# motoko_5_0.net
KiCad netlist of a schematic drawn in EAGLE
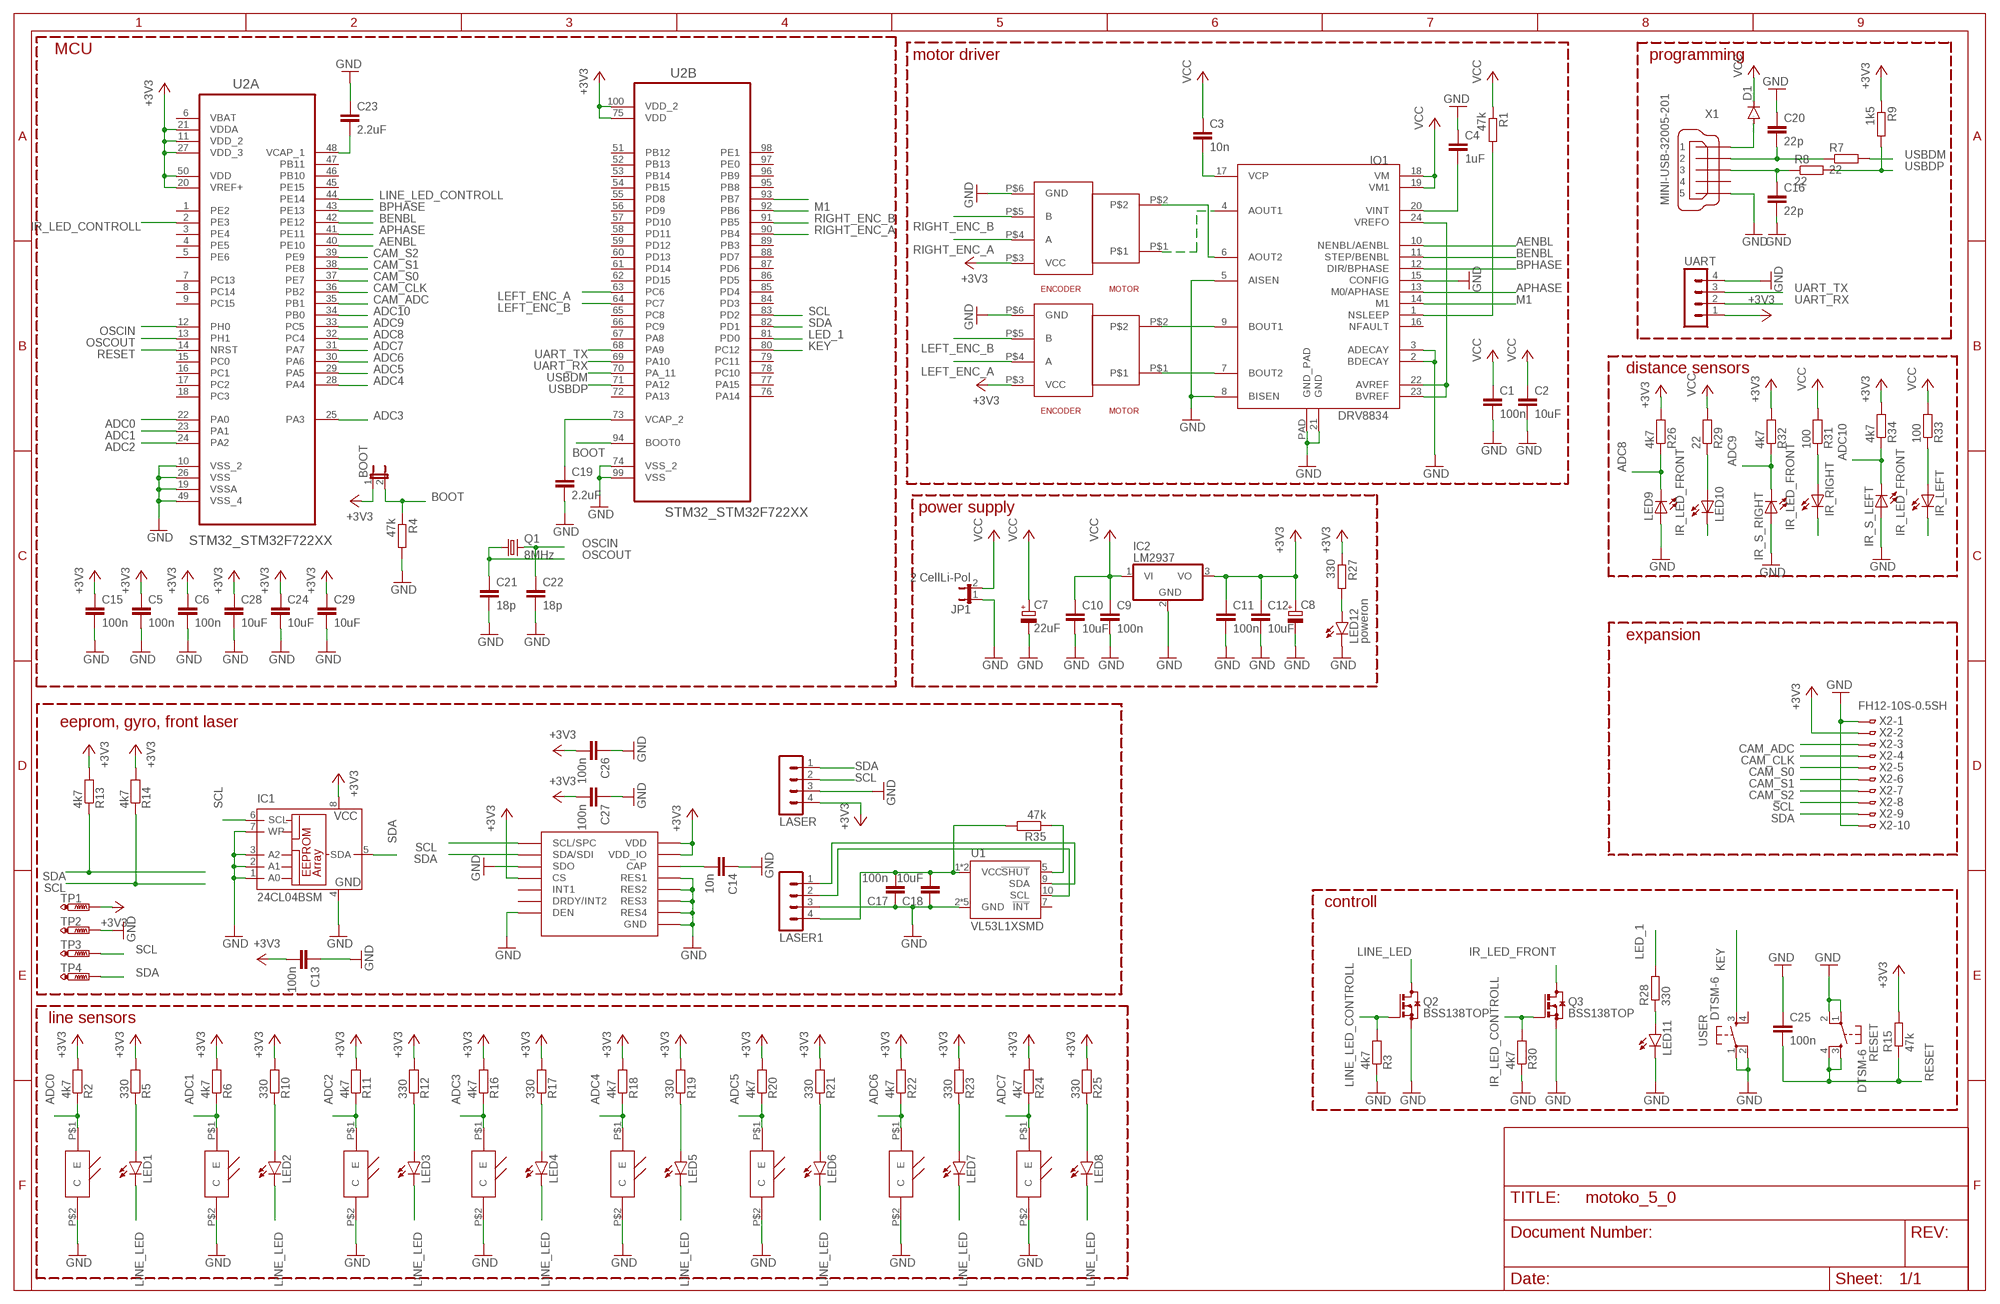
[diagram p0: schematic, sheet 1]

(export (version "E")
  (design (tool "Eeschema 10.0.6"))
  (components
    (comp (ref "BOOT")
      (value "JP1E")
      (footprint "eagle-import:JP1")
      (libsource (lib "eagle-import") (part "JP1E"))
    )
    (comp (ref "C1")
      (value "100n")
      (footprint "eagle-import:C1206")
      (libsource (lib "eagle-import") (part "C-EUC1206"))
    )
    (comp (ref "C2")
      (value "10uF")
      (footprint "eagle-import:C1206")
      (libsource (lib "eagle-import") (part "C-EUC1206"))
    )
    (comp (ref "C3")
      (value "10n")
      (footprint "eagle-import:C1206")
      (libsource (lib "eagle-import") (part "C-EUC1206"))
    )
    (comp (ref "C4")
      (value "1uF")
      (footprint "eagle-import:C1206")
      (libsource (lib "eagle-import") (part "C-EUC1206"))
    )
    (comp (ref "C5")
      (value "100n")
      (footprint "eagle-import:C0805")
      (libsource (lib "eagle-import") (part "C-EUC0805"))
    )
    (comp (ref "C6")
      (value "100n")
      (footprint "eagle-import:C0805")
      (libsource (lib "eagle-import") (part "C-EUC0805"))
    )
    (comp (ref "C7")
      (value "22uF")
      (footprint "eagle-import:153CLV-0505")
      (libsource (lib "eagle-import") (part "resistor_348_CPOL-EU153CLV-0505"))
    )
    (comp (ref "C8")
      (value "CPOL-EU140CLH-1010")
      (footprint "eagle-import:140CLH-1010")
      (libsource (lib "eagle-import") (part "CPOL-EU140CLH-1010"))
    )
    (comp (ref "C9")
      (value "100n")
      (footprint "eagle-import:C0805")
      (libsource (lib "eagle-import") (part "C-EUC0805"))
    )
    (comp (ref "C10")
      (value "10uF")
      (footprint "eagle-import:C0805")
      (libsource (lib "eagle-import") (part "C-EUC0805"))
    )
    (comp (ref "C11")
      (value "100n")
      (footprint "eagle-import:C0805")
      (libsource (lib "eagle-import") (part "C-EUC0805"))
    )
    (comp (ref "C12")
      (value "10uF")
      (footprint "eagle-import:C0805")
      (libsource (lib "eagle-import") (part "C-EUC0805"))
    )
    (comp (ref "C13")
      (value "100n")
      (footprint "eagle-import:C0805")
      (libsource (lib "eagle-import") (part "C-EUC0805"))
    )
    (comp (ref "C14")
      (value "10n")
      (footprint "eagle-import:C0805")
      (libsource (lib "eagle-import") (part "C-EUC0805"))
    )
    (comp (ref "C15")
      (value "100n")
      (footprint "eagle-import:C0805")
      (libsource (lib "eagle-import") (part "C-EUC0805"))
    )
    (comp (ref "C16")
      (value "22p")
      (footprint "eagle-import:C0805")
      (libsource (lib "eagle-import") (part "C-EUC0805"))
    )
    (comp (ref "C17")
      (value "100n")
      (footprint "eagle-import:C0805")
      (libsource (lib "eagle-import") (part "C-EUC0805"))
    )
    (comp (ref "C18")
      (value "10uF")
      (footprint "eagle-import:C0805")
      (libsource (lib "eagle-import") (part "C-EUC0805"))
    )
    (comp (ref "C19")
      (value "2.2uF")
      (footprint "eagle-import:C0805")
      (libsource (lib "eagle-import") (part "C-EUC0805"))
    )
    (comp (ref "C20")
      (value "22p")
      (footprint "eagle-import:C0805")
      (libsource (lib "eagle-import") (part "C-EUC0805"))
    )
    (comp (ref "C21")
      (value "18p")
      (footprint "eagle-import:C0805")
      (libsource (lib "eagle-import") (part "C-EUC0805"))
    )
    (comp (ref "C22")
      (value "18p")
      (footprint "eagle-import:C0805")
      (libsource (lib "eagle-import") (part "C-EUC0805"))
    )
    (comp (ref "C23")
      (value "2.2uF")
      (footprint "eagle-import:C0805")
      (libsource (lib "eagle-import") (part "C-EUC0805"))
    )
    (comp (ref "C24")
      (value "10uF")
      (footprint "eagle-import:C0805")
      (libsource (lib "eagle-import") (part "C-EUC0805"))
    )
    (comp (ref "C25")
      (value "100n")
      (footprint "eagle-import:C0805")
      (libsource (lib "eagle-import") (part "C-EUC0805"))
    )
    (comp (ref "C26")
      (value "100n")
      (footprint "eagle-import:C0805")
      (libsource (lib "eagle-import") (part "C-EUC0805"))
    )
    (comp (ref "C27")
      (value "100n")
      (footprint "eagle-import:C0805")
      (libsource (lib "eagle-import") (part "C-EUC0805"))
    )
    (comp (ref "C28")
      (value "10uF")
      (footprint "eagle-import:C0805")
      (libsource (lib "eagle-import") (part "C-EUC0805"))
    )
    (comp (ref "C29")
      (value "10uF")
      (footprint "eagle-import:C0805")
      (libsource (lib "eagle-import") (part "C-EUC0805"))
    )
    (comp (ref "D1")
      (value "DIODE-SMB")
      (footprint "eagle-import:SMB")
      (libsource (lib "eagle-import") (part "DIODE-SMB"))
    )
    (comp (ref "IC1")
      (value "24CL04BSM")
      (footprint "eagle-import:SO-08M")
      (fields (field (name "MPN") "FM24CL04-S"))
      (libsource (lib "eagle-import") (part "24SMCL04B"))
    )
    (comp (ref "IC2")
      (value "LM2937")
      (footprint "eagle-import:TO263-3")
      (libsource (lib "eagle-import") (part "LM2937"))
    )
    (comp (ref "IO1")
      (value "DRV8834")
      (footprint "eagle-import:DRV8834_PCK")
      (libsource (lib "eagle-import") (part "DRV8834"))
    )
    (comp (ref "IR_LEFT")
      (value "LED5MM")
      (footprint "eagle-import:LED5MM")
      (libsource (lib "eagle-import") (part "my_parts_LED5MM"))
    )
    (comp (ref "IR_RIGHT")
      (value "LED5MM")
      (footprint "eagle-import:LED5MM")
      (libsource (lib "eagle-import") (part "my_parts_LED5MM"))
    )
    (comp (ref "IR_S_LEFT")
      (value "LED5MM")
      (footprint "eagle-import:LED5MM")
      (libsource (lib "eagle-import") (part "my_parts_LED5MM"))
    )
    (comp (ref "IR_S_RIGHT")
      (value "LED5MM")
      (footprint "eagle-import:LED5MM")
      (libsource (lib "eagle-import") (part "my_parts_LED5MM"))
    )
    (comp (ref "JP1")
      (value "2 CellLi-Pol")
      (footprint "eagle-import:JP1")
      (libsource (lib "eagle-import") (part "JP1E"))
    )
    (comp (ref "LASER")
      (value "MA04-1")
      (footprint "eagle-import:MA04-1")
      (libsource (lib "eagle-import") (part "MA04-1"))
    )
    (comp (ref "LASER1")
      (value "MA04-1")
      (footprint "eagle-import:MA04-1")
      (libsource (lib "eagle-import") (part "MA04-1"))
    )
    (comp (ref "LED1")
      (value "LEDCHIPLED_1206")
      (footprint "eagle-import:CHIPLED_1206")
      (libsource (lib "eagle-import") (part "LEDCHIPLED_1206"))
    )
    (comp (ref "LED2")
      (value "LEDCHIPLED_1206")
      (footprint "eagle-import:CHIPLED_1206")
      (libsource (lib "eagle-import") (part "LEDCHIPLED_1206"))
    )
    (comp (ref "LED3")
      (value "LEDCHIPLED_1206")
      (footprint "eagle-import:CHIPLED_1206")
      (libsource (lib "eagle-import") (part "LEDCHIPLED_1206"))
    )
    (comp (ref "LED4")
      (value "LEDCHIPLED_1206")
      (footprint "eagle-import:CHIPLED_1206")
      (libsource (lib "eagle-import") (part "LEDCHIPLED_1206"))
    )
    (comp (ref "LED5")
      (value "LEDCHIPLED_1206")
      (footprint "eagle-import:CHIPLED_1206")
      (libsource (lib "eagle-import") (part "LEDCHIPLED_1206"))
    )
    (comp (ref "LED6")
      (value "LEDCHIPLED_1206")
      (footprint "eagle-import:CHIPLED_1206")
      (libsource (lib "eagle-import") (part "LEDCHIPLED_1206"))
    )
    (comp (ref "LED7")
      (value "LEDCHIPLED_1206")
      (footprint "eagle-import:CHIPLED_1206")
      (libsource (lib "eagle-import") (part "LEDCHIPLED_1206"))
    )
    (comp (ref "LED8")
      (value "LEDCHIPLED_1206")
      (footprint "eagle-import:CHIPLED_1206")
      (libsource (lib "eagle-import") (part "LEDCHIPLED_1206"))
    )
    (comp (ref "LED9")
      (value "LED5MM")
      (footprint "eagle-import:LED5MM")
      (libsource (lib "eagle-import") (part "my_parts_LED5MM"))
    )
    (comp (ref "LED10")
      (value "LED5MM")
      (footprint "eagle-import:LED5MM")
      (libsource (lib "eagle-import") (part "my_parts_LED5MM"))
    )
    (comp (ref "LED11")
      (value "LEDCHIPLED_1206")
      (footprint "eagle-import:CHIPLED_1206")
      (libsource (lib "eagle-import") (part "LEDCHIPLED_1206"))
    )
    (comp (ref "LED12")
      (value "poweron")
      (footprint "eagle-import:CHIPLED_1206")
      (libsource (lib "eagle-import") (part "LEDCHIPLED_1206"))
    )
    (comp (ref "LSM6DS0")
      (value "ST_L3GD20H")
      (footprint "eagle-import:ST_LGA16L")
      (libsource (lib "eagle-import") (part "ST_L3GD20H"))
    )
    (comp (ref "Q1")
      (value "8MHz")
      (footprint "eagle-import:CTS406")
      (libsource (lib "eagle-import") (part "CRYSTALCTS406"))
    )
    (comp (ref "Q2")
      (value "BSS138TOP")
      (footprint "eagle-import:SOT23")
      (libsource (lib "eagle-import") (part "BSS138TOP"))
    )
    (comp (ref "Q3")
      (value "BSS138TOP")
      (footprint "eagle-import:SOT23")
      (libsource (lib "eagle-import") (part "BSS138TOP"))
    )
    (comp (ref "R1")
      (value "47k")
      (footprint "eagle-import:M1206")
      (libsource (lib "eagle-import") (part "R-EU_M1206"))
    )
    (comp (ref "R2")
      (value "4k7")
      (footprint "eagle-import:M0805")
      (libsource (lib "eagle-import") (part "R-EU_M0805"))
    )
    (comp (ref "R3")
      (value "4k7")
      (footprint "eagle-import:M0805")
      (libsource (lib "eagle-import") (part "R-EU_M0805"))
    )
    (comp (ref "R4")
      (value "47k")
      (footprint "eagle-import:M0805")
      (libsource (lib "eagle-import") (part "R-EU_M0805"))
    )
    (comp (ref "R5")
      (value "330")
      (footprint "eagle-import:M0805")
      (libsource (lib "eagle-import") (part "R-EU_M0805"))
    )
    (comp (ref "R6")
      (value "4k7")
      (footprint "eagle-import:M0805")
      (libsource (lib "eagle-import") (part "R-EU_M0805"))
    )
    (comp (ref "R7")
      (value "22")
      (footprint "eagle-import:M0805")
      (libsource (lib "eagle-import") (part "R-EU_M0805"))
    )
    (comp (ref "R8")
      (value "22")
      (footprint "eagle-import:M0805")
      (libsource (lib "eagle-import") (part "R-EU_M0805"))
    )
    (comp (ref "R9")
      (value "1k5")
      (footprint "eagle-import:M0805")
      (libsource (lib "eagle-import") (part "R-EU_M0805"))
    )
    (comp (ref "R10")
      (value "330")
      (footprint "eagle-import:M0805")
      (libsource (lib "eagle-import") (part "R-EU_M0805"))
    )
    (comp (ref "R11")
      (value "4k7")
      (footprint "eagle-import:M0805")
      (libsource (lib "eagle-import") (part "R-EU_M0805"))
    )
    (comp (ref "R12")
      (value "330")
      (footprint "eagle-import:M0805")
      (libsource (lib "eagle-import") (part "R-EU_M0805"))
    )
    (comp (ref "R13")
      (value "4k7")
      (footprint "eagle-import:M0805")
      (libsource (lib "eagle-import") (part "R-EU_M0805"))
    )
    (comp (ref "R14")
      (value "4k7")
      (footprint "eagle-import:M0805")
      (libsource (lib "eagle-import") (part "R-EU_M0805"))
    )
    (comp (ref "R15")
      (value "47k")
      (footprint "eagle-import:M0805")
      (libsource (lib "eagle-import") (part "R-EU_M0805"))
    )
    (comp (ref "R16")
      (value "4k7")
      (footprint "eagle-import:M0805")
      (libsource (lib "eagle-import") (part "R-EU_M0805"))
    )
    (comp (ref "R17")
      (value "330")
      (footprint "eagle-import:M0805")
      (libsource (lib "eagle-import") (part "R-EU_M0805"))
    )
    (comp (ref "R18")
      (value "4k7")
      (footprint "eagle-import:M0805")
      (libsource (lib "eagle-import") (part "R-EU_M0805"))
    )
    (comp (ref "R19")
      (value "330")
      (footprint "eagle-import:M0805")
      (libsource (lib "eagle-import") (part "R-EU_M0805"))
    )
    (comp (ref "R20")
      (value "4k7")
      (footprint "eagle-import:M0805")
      (libsource (lib "eagle-import") (part "R-EU_M0805"))
    )
    (comp (ref "R21")
      (value "330")
      (footprint "eagle-import:M0805")
      (libsource (lib "eagle-import") (part "R-EU_M0805"))
    )
    (comp (ref "R22")
      (value "4k7")
      (footprint "eagle-import:M0805")
      (libsource (lib "eagle-import") (part "R-EU_M0805"))
    )
    (comp (ref "R23")
      (value "330")
      (footprint "eagle-import:M0805")
      (libsource (lib "eagle-import") (part "R-EU_M0805"))
    )
    (comp (ref "R24")
      (value "4k7")
      (footprint "eagle-import:M0805")
      (libsource (lib "eagle-import") (part "R-EU_M0805"))
    )
    (comp (ref "R25")
      (value "330")
      (footprint "eagle-import:M0805")
      (libsource (lib "eagle-import") (part "R-EU_M0805"))
    )
    (comp (ref "R26")
      (value "4k7")
      (footprint "eagle-import:M0805")
      (libsource (lib "eagle-import") (part "R-EU_M0805"))
    )
    (comp (ref "R27")
      (value "330")
      (footprint "eagle-import:M0805")
      (libsource (lib "eagle-import") (part "R-EU_M0805"))
    )
    (comp (ref "R28")
      (value "330")
      (footprint "eagle-import:M0805")
      (libsource (lib "eagle-import") (part "R-EU_M0805"))
    )
    (comp (ref "R29")
      (value "22")
      (footprint "eagle-import:M0805")
      (libsource (lib "eagle-import") (part "R-EU_M0805"))
    )
    (comp (ref "R30")
      (value "4k7")
      (footprint "eagle-import:M0805")
      (libsource (lib "eagle-import") (part "R-EU_M0805"))
    )
    (comp (ref "R31")
      (value "100")
      (footprint "eagle-import:M0805")
      (libsource (lib "eagle-import") (part "R-EU_M0805"))
    )
    (comp (ref "R32")
      (value "4k7")
      (footprint "eagle-import:M0805")
      (libsource (lib "eagle-import") (part "R-EU_M0805"))
    )
    (comp (ref "R33")
      (value "100")
      (footprint "eagle-import:M0805")
      (libsource (lib "eagle-import") (part "R-EU_M0805"))
    )
    (comp (ref "R34")
      (value "4k7")
      (footprint "eagle-import:M0805")
      (libsource (lib "eagle-import") (part "R-EU_M0805"))
    )
    (comp (ref "R35")
      (value "47k")
      (footprint "eagle-import:M0805")
      (libsource (lib "eagle-import") (part "R-EU_M0805"))
    )
    (comp (ref "RESET")
      (value "DTSM-6")
      (footprint "eagle-import:DTSM-6")
      (libsource (lib "eagle-import") (part "DTSM-6"))
    )
    (comp (ref "TP1")
      (value "PTR1B1,27")
      (footprint "eagle-import:B1,27")
      (libsource (lib "eagle-import") (part "PTR1B1,27"))
    )
    (comp (ref "TP2")
      (value "PTR1B1,27")
      (footprint "eagle-import:B1,27")
      (libsource (lib "eagle-import") (part "PTR1B1,27"))
    )
    (comp (ref "TP3")
      (value "PTR1B1,27")
      (footprint "eagle-import:B1,27")
      (libsource (lib "eagle-import") (part "PTR1B1,27"))
    )
    (comp (ref "TP4")
      (value "PTR1B1,27")
      (footprint "eagle-import:B1,27")
      (libsource (lib "eagle-import") (part "PTR1B1,27"))
    )
    (comp (ref "U$3")
      (value "SFH3710")
      (footprint "eagle-import:SFH3710")
      (libsource (lib "eagle-import") (part "SFH3710"))
    )
    (comp (ref "U$4")
      (value "SFH3710")
      (footprint "eagle-import:SFH3710")
      (libsource (lib "eagle-import") (part "SFH3710"))
    )
    (comp (ref "U$5")
      (value "SFH3710")
      (footprint "eagle-import:SFH3710")
      (libsource (lib "eagle-import") (part "SFH3710"))
    )
    (comp (ref "U$6")
      (value "SFH3710")
      (footprint "eagle-import:SFH3710")
      (libsource (lib "eagle-import") (part "SFH3710"))
    )
    (comp (ref "U$7")
      (value "SFH3710")
      (footprint "eagle-import:SFH3710")
      (libsource (lib "eagle-import") (part "SFH3710"))
    )
    (comp (ref "U$8")
      (value "SFH3710")
      (footprint "eagle-import:SFH3710")
      (libsource (lib "eagle-import") (part "SFH3710"))
    )
    (comp (ref "U$9")
      (value "SFH3710")
      (footprint "eagle-import:SFH3710")
      (libsource (lib "eagle-import") (part "SFH3710"))
    )
    (comp (ref "U$10")
      (value "SFH3710")
      (footprint "eagle-import:SFH3710")
      (libsource (lib "eagle-import") (part "SFH3710"))
    )
    (comp (ref "U$11")
      (value "POLOLU_GEAR_MOTORPOLO")
      (footprint "eagle-import:POLOLU_GEAR_MOTOR")
      (libsource (lib "eagle-import") (part "POLOLU_GEAR_MOTORPOLO"))
    )
    (comp (ref "U$12")
      (value "POLOLU_GEAR_MOTORPOLO")
      (footprint "eagle-import:POLOLU_GEAR_MOTOR")
      (libsource (lib "eagle-import") (part "POLOLU_GEAR_MOTORPOLO"))
    )
    (comp (ref "U1")
      (value "VL53L1XSMD")
      (footprint "eagle-import:VL53L1X")
      (libsource (lib "eagle-import") (part "VL53L1XSMD"))
    )
    (comp (ref "U2")
      (value "STM32_STM32F722XX")
      (footprint "eagle-import:STM32_QFP50P1600X1600X160-100N")
      (fields (field (name "MPN") "STM32F407VET6"))
      (libsource (lib "eagle-import") (part "STM32_STM32F722XX"))
    )
    (comp (ref "UART")
      (value "MA04-1")
      (footprint "eagle-import:MA04-1")
      (libsource (lib "eagle-import") (part "MA04-1"))
    )
    (comp (ref "USER")
      (value "DTSM-6")
      (footprint "eagle-import:DTSM-6")
      (libsource (lib "eagle-import") (part "DTSM-6"))
    )
    (comp (ref "X1")
      (value "MINI-USB-32005-201")
      (footprint "eagle-import:32005-201")
      (libsource (lib "eagle-import") (part "MINI-USB-32005-201"))
    )
    (comp (ref "X2")
      (value "FH12-10S-0.5SH")
      (footprint "eagle-import:FH12-10S-0.5SH")
      (fields (field (name "MPN") "FH12-10S-0.5SH(55)"))
      (libsource (lib "eagle-import") (part "FH12-10S-0.5SH"))
    )
  )
  (nets
    (net (code "1") (name "+3V3") (class "Default")
      (node (ref "BOOT") (pin "1") (pinfunction "1_1") (pintype "passive"))
      (node (ref "C11") (pin "1") (pinfunction "1_1") (pintype "passive"))
      (node (ref "C12") (pin "1") (pinfunction "1_1") (pintype "passive"))
      (node (ref "C13") (pin "2") (pinfunction "2_2") (pintype "passive"))
      (node (ref "C15") (pin "1") (pinfunction "1_1") (pintype "passive"))
      (node (ref "C24") (pin "1") (pinfunction "1_1") (pintype "passive"))
      (node (ref "C26") (pin "2") (pinfunction "2_2") (pintype "passive"))
      (node (ref "C27") (pin "2") (pinfunction "2_2") (pintype "passive"))
      (node (ref "C28") (pin "1") (pinfunction "1_1") (pintype "passive"))
      (node (ref "C29") (pin "1") (pinfunction "1_1") (pintype "passive"))
      (node (ref "C5") (pin "1") (pinfunction "1_1") (pintype "passive"))
      (node (ref "C6") (pin "1") (pinfunction "1_1") (pintype "passive"))
      (node (ref "C8") (pin "+") (pinfunction "+_+") (pintype "passive"))
      (node (ref "IC1") (pin "8") (pinfunction "VCC_8") (pintype "power_in"))
      (node (ref "IC2") (pin "3") (pinfunction "VO_3") (pintype "passive"))
      (node (ref "LASER") (pin "4") (pinfunction "4_4") (pintype "passive"))
      (node (ref "LSM6DS0") (pin "P$1") (pinfunction "VDD_IO_P$1") (pintype "power_in"))
      (node (ref "LSM6DS0") (pin "P$16") (pinfunction "VDD_P$16") (pintype "power_in"))
      (node (ref "LSM6DS0") (pin "P$5") (pinfunction "CS_P$5") (pintype "bidirectional"))
      (node (ref "R10") (pin "2") (pinfunction "2_2") (pintype "passive"))
      (node (ref "R11") (pin "2") (pinfunction "2_2") (pintype "passive"))
      (node (ref "R12") (pin "2") (pinfunction "2_2") (pintype "passive"))
      (node (ref "R13") (pin "2") (pinfunction "2_2") (pintype "passive"))
      (node (ref "R14") (pin "2") (pinfunction "2_2") (pintype "passive"))
      (node (ref "R15") (pin "2") (pinfunction "2_2") (pintype "passive"))
      (node (ref "R16") (pin "2") (pinfunction "2_2") (pintype "passive"))
      (node (ref "R17") (pin "2") (pinfunction "2_2") (pintype "passive"))
      (node (ref "R18") (pin "2") (pinfunction "2_2") (pintype "passive"))
      (node (ref "R19") (pin "2") (pinfunction "2_2") (pintype "passive"))
      (node (ref "R2") (pin "2") (pinfunction "2_2") (pintype "passive"))
      (node (ref "R20") (pin "2") (pinfunction "2_2") (pintype "passive"))
      (node (ref "R21") (pin "2") (pinfunction "2_2") (pintype "passive"))
      (node (ref "R22") (pin "2") (pinfunction "2_2") (pintype "passive"))
      (node (ref "R23") (pin "2") (pinfunction "2_2") (pintype "passive"))
      (node (ref "R24") (pin "2") (pinfunction "2_2") (pintype "passive"))
      (node (ref "R25") (pin "2") (pinfunction "2_2") (pintype "passive"))
      (node (ref "R26") (pin "2") (pinfunction "2_2") (pintype "passive"))
      (node (ref "R27") (pin "1") (pinfunction "1_1") (pintype "passive"))
      (node (ref "R32") (pin "2") (pinfunction "2_2") (pintype "passive"))
      (node (ref "R34") (pin "2") (pinfunction "2_2") (pintype "passive"))
      (node (ref "R5") (pin "2") (pinfunction "2_2") (pintype "passive"))
      (node (ref "R6") (pin "2") (pinfunction "2_2") (pintype "passive"))
      (node (ref "R9") (pin "1") (pinfunction "1_1") (pintype "passive"))
      (node (ref "TP1") (pin "TP") (pinfunction "TP_TP") (pintype "input"))
      (node (ref "U$11") (pin "P$3") (pinfunction "VCC_P$3") (pintype "bidirectional"))
      (node (ref "U$12") (pin "P$3") (pinfunction "VCC_P$3") (pintype "bidirectional"))
      (node (ref "U2") (pin "100") (pinfunction "VDD_2_100") (pintype "power_in"))
      (node (ref "U2") (pin "11") (pinfunction "VDD_2_11") (pintype "power_in"))
      (node (ref "U2") (pin "20") (pinfunction "VREF+_20") (pintype "power_in"))
      (node (ref "U2") (pin "21") (pinfunction "VDDA_21") (pintype "power_in"))
      (node (ref "U2") (pin "27") (pinfunction "VDD_3_27") (pintype "power_in"))
      (node (ref "U2") (pin "50") (pinfunction "VDD_50") (pintype "power_in"))
      (node (ref "U2") (pin "75") (pinfunction "VDD_75") (pintype "power_in"))
      (node (ref "UART") (pin "1") (pinfunction "1_1") (pintype "passive"))
      (node (ref "X2") (pin "2") (pinfunction "1_2") (pintype "passive"))
    )
    (net (code "2") (name "/ADC0") (class "Default")
      (node (ref "R2") (pin "1") (pinfunction "1_1") (pintype "passive"))
      (node (ref "U$3") (pin "P$1") (pinfunction "E_P$1") (pintype "bidirectional"))
      (node (ref "U2") (pin "22") (pinfunction "PA0_22") (pintype "bidirectional"))
    )
    (net (code "3") (name "/ADC1") (class "Default")
      (node (ref "R6") (pin "1") (pinfunction "1_1") (pintype "passive"))
      (node (ref "U$4") (pin "P$1") (pinfunction "E_P$1") (pintype "bidirectional"))
      (node (ref "U2") (pin "23") (pinfunction "PA1_23") (pintype "bidirectional"))
    )
    (net (code "4") (name "/ADC2") (class "Default")
      (node (ref "R11") (pin "1") (pinfunction "1_1") (pintype "passive"))
      (node (ref "U$5") (pin "P$1") (pinfunction "E_P$1") (pintype "bidirectional"))
      (node (ref "U2") (pin "24") (pinfunction "PA2_24") (pintype "bidirectional"))
    )
    (net (code "5") (name "/ADC3") (class "Default")
      (node (ref "R16") (pin "1") (pinfunction "1_1") (pintype "passive"))
      (node (ref "U$6") (pin "P$1") (pinfunction "E_P$1") (pintype "bidirectional"))
      (node (ref "U2") (pin "25") (pinfunction "PA3_25") (pintype "bidirectional"))
    )
    (net (code "6") (name "/ADC4") (class "Default")
      (node (ref "R18") (pin "1") (pinfunction "1_1") (pintype "passive"))
      (node (ref "U$7") (pin "P$1") (pinfunction "E_P$1") (pintype "bidirectional"))
      (node (ref "U2") (pin "28") (pinfunction "PA4_28") (pintype "bidirectional"))
    )
    (net (code "7") (name "/ADC5") (class "Default")
      (node (ref "R20") (pin "1") (pinfunction "1_1") (pintype "passive"))
      (node (ref "U$8") (pin "P$1") (pinfunction "E_P$1") (pintype "bidirectional"))
      (node (ref "U2") (pin "29") (pinfunction "PA5_29") (pintype "bidirectional"))
    )
    (net (code "8") (name "/ADC6") (class "Default")
      (node (ref "R22") (pin "1") (pinfunction "1_1") (pintype "passive"))
      (node (ref "U$9") (pin "P$1") (pinfunction "E_P$1") (pintype "bidirectional"))
      (node (ref "U2") (pin "30") (pinfunction "PA6_30") (pintype "bidirectional"))
    )
    (net (code "9") (name "/ADC7") (class "Default")
      (node (ref "R24") (pin "1") (pinfunction "1_1") (pintype "passive"))
      (node (ref "U$10") (pin "P$1") (pinfunction "E_P$1") (pintype "bidirectional"))
      (node (ref "U2") (pin "31") (pinfunction "PA7_31") (pintype "bidirectional"))
    )
    (net (code "10") (name "/ADC8") (class "Default")
      (node (ref "LED9") (pin "K") (pinfunction "C_K") (pintype "passive"))
      (node (ref "R26") (pin "1") (pinfunction "1_1") (pintype "passive"))
      (node (ref "U2") (pin "32") (pinfunction "PC4_32") (pintype "bidirectional"))
    )
    (net (code "11") (name "/ADC9") (class "Default")
      (node (ref "IR_S_RIGHT") (pin "K") (pinfunction "C_K") (pintype "passive"))
      (node (ref "R32") (pin "1") (pinfunction "1_1") (pintype "passive"))
      (node (ref "U2") (pin "33") (pinfunction "PC5_33") (pintype "bidirectional"))
    )
    (net (code "12") (name "/ADC10") (class "Default")
      (node (ref "IR_S_LEFT") (pin "K") (pinfunction "C_K") (pintype "passive"))
      (node (ref "R34") (pin "1") (pinfunction "1_1") (pintype "passive"))
      (node (ref "U2") (pin "34") (pinfunction "PB0_34") (pintype "bidirectional"))
    )
    (net (code "13") (name "/AENBL") (class "Default")
      (node (ref "IO1") (pin "10") (pinfunction "NENBL/AENBL_10") (pintype "bidirectional"))
      (node (ref "U2") (pin "40") (pinfunction "PE10_40") (pintype "bidirectional"))
    )
    (net (code "14") (name "/APHASE") (class "Default")
      (node (ref "IO1") (pin "13") (pinfunction "M0/APHASE_13") (pintype "bidirectional"))
      (node (ref "U2") (pin "41") (pinfunction "PE11_41") (pintype "bidirectional"))
    )
    (net (code "15") (name "/BENBL") (class "Default")
      (node (ref "IO1") (pin "11") (pinfunction "STEP/BENBL_11") (pintype "bidirectional"))
      (node (ref "U2") (pin "42") (pinfunction "PE12_42") (pintype "bidirectional"))
    )
    (net (code "16") (name "/BOOT") (class "Default")
      (node (ref "BOOT") (pin "2") (pinfunction "2_2") (pintype "passive"))
      (node (ref "R4") (pin "1") (pinfunction "1_1") (pintype "passive"))
      (node (ref "U2") (pin "94") (pinfunction "BOOT0_94") (pintype "input"))
    )
    (net (code "17") (name "/BPHASE") (class "Default")
      (node (ref "IO1") (pin "12") (pinfunction "DIR/BPHASE_12") (pintype "bidirectional"))
      (node (ref "U2") (pin "43") (pinfunction "PE13_43") (pintype "bidirectional"))
    )
    (net (code "18") (name "/CAM_ADC") (class "Default")
      (node (ref "U2") (pin "35") (pinfunction "PB1_35") (pintype "bidirectional"))
      (node (ref "X2") (pin "3") (pinfunction "1_3") (pintype "passive"))
    )
    (net (code "19") (name "/CAM_CLK") (class "Default")
      (node (ref "U2") (pin "36") (pinfunction "PB2_36") (pintype "bidirectional"))
      (node (ref "X2") (pin "4") (pinfunction "1_4") (pintype "passive"))
    )
    (net (code "20") (name "/CAM_S0") (class "Default")
      (node (ref "U2") (pin "37") (pinfunction "PE7_37") (pintype "bidirectional"))
      (node (ref "X2") (pin "5") (pinfunction "1_5") (pintype "passive"))
    )
    (net (code "21") (name "/CAM_S1") (class "Default")
      (node (ref "U2") (pin "38") (pinfunction "PE8_38") (pintype "bidirectional"))
      (node (ref "X2") (pin "6") (pinfunction "1_6") (pintype "passive"))
    )
    (net (code "22") (name "/CAM_S2") (class "Default")
      (node (ref "U2") (pin "39") (pinfunction "PE9_39") (pintype "bidirectional"))
      (node (ref "X2") (pin "7") (pinfunction "1_7") (pintype "passive"))
    )
    (net (code "23") (name "/IR_LED_CONTROLL") (class "Default")
      (node (ref "Q3") (pin "1") (pinfunction "G_1") (pintype "passive"))
      (node (ref "R30") (pin "2") (pinfunction "2_2") (pintype "passive"))
      (node (ref "U2") (pin "2") (pinfunction "PE3_2") (pintype "bidirectional"))
    )
    (net (code "24") (name "/IR_LED_FRONT") (class "Default")
      (node (ref "IR_LEFT") (pin "K") (pinfunction "C_K") (pintype "passive"))
      (node (ref "IR_RIGHT") (pin "K") (pinfunction "C_K") (pintype "passive"))
      (node (ref "LED10") (pin "K") (pinfunction "C_K") (pintype "passive"))
      (node (ref "Q3") (pin "3") (pinfunction "D_3") (pintype "passive"))
    )
    (net (code "25") (name "/KEY") (class "Default")
      (node (ref "U2") (pin "80") (pinfunction "PC12_80") (pintype "bidirectional"))
      (node (ref "USER") (pin "3") (pinfunction "3_3") (pintype "passive"))
    )
    (net (code "26") (name "/LED_1") (class "Default")
      (node (ref "R28") (pin "2") (pinfunction "2_2") (pintype "passive"))
      (node (ref "U2") (pin "81") (pinfunction "PD0_81") (pintype "bidirectional"))
    )
    (net (code "27") (name "/LEFT_ENC_A") (class "Default")
      (node (ref "U$11") (pin "P$4") (pinfunction "A_P$4") (pintype "bidirectional"))
      (node (ref "U2") (pin "63") (pinfunction "PC6_63") (pintype "bidirectional"))
    )
    (net (code "28") (name "/LEFT_ENC_B") (class "Default")
      (node (ref "U$11") (pin "P$5") (pinfunction "B_P$5") (pintype "bidirectional"))
      (node (ref "U2") (pin "64") (pinfunction "PC7_64") (pintype "bidirectional"))
    )
    (net (code "29") (name "/LINE_LED") (class "Default")
      (node (ref "LED1") (pin "C") (pinfunction "C_C") (pintype "passive"))
      (node (ref "LED2") (pin "C") (pinfunction "C_C") (pintype "passive"))
      (node (ref "LED3") (pin "C") (pinfunction "C_C") (pintype "passive"))
      (node (ref "LED4") (pin "C") (pinfunction "C_C") (pintype "passive"))
      (node (ref "LED5") (pin "C") (pinfunction "C_C") (pintype "passive"))
      (node (ref "LED6") (pin "C") (pinfunction "C_C") (pintype "passive"))
      (node (ref "LED7") (pin "C") (pinfunction "C_C") (pintype "passive"))
      (node (ref "LED8") (pin "C") (pinfunction "C_C") (pintype "passive"))
      (node (ref "Q2") (pin "3") (pinfunction "D_3") (pintype "passive"))
    )
    (net (code "30") (name "/LINE_LED_CONTROLL") (class "Default")
      (node (ref "Q2") (pin "1") (pinfunction "G_1") (pintype "passive"))
      (node (ref "R3") (pin "2") (pinfunction "2_2") (pintype "passive"))
      (node (ref "U2") (pin "44") (pinfunction "PE14_44") (pintype "bidirectional"))
    )
    (net (code "31") (name "/M1") (class "Default")
      (node (ref "IO1") (pin "14") (pinfunction "M1_14") (pintype "bidirectional"))
      (node (ref "U2") (pin "92") (pinfunction "PB6_92") (pintype "bidirectional"))
    )
    (net (code "32") (name "/OSCIN") (class "Default")
      (node (ref "C22") (pin "1") (pinfunction "1_1") (pintype "passive"))
      (node (ref "Q1") (pin "3") (pinfunction "2_3") (pintype "passive"))
      (node (ref "U2") (pin "12") (pinfunction "PH0_12") (pintype "bidirectional"))
    )
    (net (code "33") (name "/OSCOUT") (class "Default")
      (node (ref "C21") (pin "1") (pinfunction "1_1") (pintype "passive"))
      (node (ref "Q1") (pin "1") (pinfunction "1_1") (pintype "passive"))
      (node (ref "U2") (pin "13") (pinfunction "PH1_13") (pintype "bidirectional"))
    )
    (net (code "34") (name "/RESET") (class "Default")
      (node (ref "C25") (pin "2") (pinfunction "2_2") (pintype "passive"))
      (node (ref "R15") (pin "1") (pinfunction "1_1") (pintype "passive"))
      (node (ref "RESET") (pin "3") (pinfunction "3_3") (pintype "passive"))
      (node (ref "RESET") (pin "4") (pinfunction "4_4") (pintype "passive"))
      (node (ref "U2") (pin "14") (pinfunction "NRST_14") (pintype "bidirectional"))
    )
    (net (code "35") (name "/RIGHT_ENC_A") (class "Default")
      (node (ref "U$12") (pin "P$4") (pinfunction "A_P$4") (pintype "bidirectional"))
      (node (ref "U2") (pin "90") (pinfunction "PB4_90") (pintype "bidirectional"))
    )
    (net (code "36") (name "/RIGHT_ENC_B") (class "Default")
      (node (ref "U$12") (pin "P$5") (pinfunction "B_P$5") (pintype "bidirectional"))
      (node (ref "U2") (pin "91") (pinfunction "PB5_91") (pintype "bidirectional"))
    )
    (net (code "37") (name "/SCL") (class "Default")
      (node (ref "IC1") (pin "6") (pinfunction "SCL_6") (pintype "input"))
      (node (ref "LASER") (pin "2") (pinfunction "2_2") (pintype "passive"))
      (node (ref "LSM6DS0") (pin "P$2") (pinfunction "SCL/SPC_P$2") (pintype "bidirectional"))
      (node (ref "R14") (pin "1") (pinfunction "1_1") (pintype "passive"))
      (node (ref "TP3") (pin "TP") (pinfunction "TP_TP") (pintype "input"))
      (node (ref "U2") (pin "83") (pinfunction "PD2_83") (pintype "bidirectional"))
      (node (ref "X2") (pin "8") (pinfunction "1_8") (pintype "passive"))
    )
    (net (code "38") (name "/SDA") (class "Default")
      (node (ref "IC1") (pin "5") (pinfunction "SDA_5") (pintype "bidirectional"))
      (node (ref "LASER") (pin "1") (pinfunction "1_1") (pintype "passive"))
      (node (ref "LSM6DS0") (pin "P$3") (pinfunction "SDA/SDI_P$3") (pintype "bidirectional"))
      (node (ref "R13") (pin "1") (pinfunction "1_1") (pintype "passive"))
      (node (ref "TP4") (pin "TP") (pinfunction "TP_TP") (pintype "input"))
      (node (ref "U2") (pin "82") (pinfunction "PD1_82") (pintype "bidirectional"))
      (node (ref "X2") (pin "9") (pinfunction "1_9") (pintype "passive"))
    )
    (net (code "39") (name "/UART_RX") (class "Default")
      (node (ref "U2") (pin "69") (pinfunction "PA10_69") (pintype "bidirectional"))
      (node (ref "UART") (pin "2") (pinfunction "2_2") (pintype "passive"))
    )
    (net (code "40") (name "/UART_TX") (class "Default")
      (node (ref "U2") (pin "68") (pinfunction "PA9_68") (pintype "bidirectional"))
      (node (ref "UART") (pin "3") (pinfunction "3_3") (pintype "passive"))
    )
    (net (code "41") (name "/USBDM") (class "Default")
      (node (ref "R7") (pin "2") (pinfunction "2_2") (pintype "passive"))
      (node (ref "U2") (pin "70") (pinfunction "PA_11_70") (pintype "bidirectional"))
    )
    (net (code "42") (name "/USBDP") (class "Default")
      (node (ref "R8") (pin "2") (pinfunction "2_2") (pintype "passive"))
      (node (ref "R9") (pin "2") (pinfunction "2_2") (pintype "passive"))
      (node (ref "U2") (pin "71") (pinfunction "PA12_71") (pintype "bidirectional"))
    )
    (net (code "43") (name "/VBAT") (class "Default")
      (node (ref "U2") (pin "6") (pinfunction "VBAT_6") (pintype "power_in"))
    )
    (net (code "44") (name "GND") (class "Default")
      (node (ref "C1") (pin "2") (pinfunction "2_2") (pintype "passive"))
      (node (ref "C10") (pin "2") (pinfunction "2_2") (pintype "passive"))
      (node (ref "C11") (pin "2") (pinfunction "2_2") (pintype "passive"))
      (node (ref "C12") (pin "2") (pinfunction "2_2") (pintype "passive"))
      (node (ref "C13") (pin "1") (pinfunction "1_1") (pintype "passive"))
      (node (ref "C14") (pin "1") (pinfunction "1_1") (pintype "passive"))
      (node (ref "C15") (pin "2") (pinfunction "2_2") (pintype "passive"))
      (node (ref "C16") (pin "2") (pinfunction "2_2") (pintype "passive"))
      (node (ref "C17") (pin "1") (pinfunction "1_1") (pintype "passive"))
      (node (ref "C18") (pin "1") (pinfunction "1_1") (pintype "passive"))
      (node (ref "C19") (pin "2") (pinfunction "2_2") (pintype "passive"))
      (node (ref "C2") (pin "2") (pinfunction "2_2") (pintype "passive"))
      (node (ref "C20") (pin "1") (pinfunction "1_1") (pintype "passive"))
      (node (ref "C21") (pin "2") (pinfunction "2_2") (pintype "passive"))
      (node (ref "C22") (pin "2") (pinfunction "2_2") (pintype "passive"))
      (node (ref "C23") (pin "1") (pinfunction "1_1") (pintype "passive"))
      (node (ref "C24") (pin "2") (pinfunction "2_2") (pintype "passive"))
      (node (ref "C25") (pin "1") (pinfunction "1_1") (pintype "passive"))
      (node (ref "C26") (pin "1") (pinfunction "1_1") (pintype "passive"))
      (node (ref "C27") (pin "1") (pinfunction "1_1") (pintype "passive"))
      (node (ref "C28") (pin "2") (pinfunction "2_2") (pintype "passive"))
      (node (ref "C29") (pin "2") (pinfunction "2_2") (pintype "passive"))
      (node (ref "C4") (pin "1") (pinfunction "1_1") (pintype "passive"))
      (node (ref "C5") (pin "2") (pinfunction "2_2") (pintype "passive"))
      (node (ref "C6") (pin "2") (pinfunction "2_2") (pintype "passive"))
      (node (ref "C7") (pin "-") (pinfunction "-_-") (pintype "passive"))
      (node (ref "C8") (pin "-") (pinfunction "-_-") (pintype "passive"))
      (node (ref "C9") (pin "2") (pinfunction "2_2") (pintype "passive"))
      (node (ref "IC1") (pin "1") (pinfunction "A0_1") (pintype "input"))
      (node (ref "IC1") (pin "2") (pinfunction "A1_2") (pintype "input"))
      (node (ref "IC1") (pin "3") (pinfunction "A2_3") (pintype "input"))
      (node (ref "IC1") (pin "4") (pinfunction "GND_4") (pintype "power_in"))
      (node (ref "IC1") (pin "7") (pinfunction "WP_7") (pintype "input"))
      (node (ref "IC2") (pin "2") (pinfunction "GND_2") (pintype "passive"))
      (node (ref "IO1") (pin "15") (pinfunction "CONFIG_15") (pintype "bidirectional"))
      (node (ref "IO1") (pin "2") (pinfunction "BDECAY_2") (pintype "bidirectional"))
      (node (ref "IO1") (pin "21") (pinfunction "GND_21") (pintype "bidirectional"))
      (node (ref "IO1") (pin "3") (pinfunction "ADECAY_3") (pintype "bidirectional"))
      (node (ref "IO1") (pin "5") (pinfunction "AISEN_5") (pintype "bidirectional"))
      (node (ref "IO1") (pin "8") (pinfunction "BISEN_8") (pintype "bidirectional"))
      (node (ref "IO1") (pin "PAD") (pinfunction "GND_PAD_PAD") (pintype "bidirectional"))
      (node (ref "IR_S_LEFT") (pin "A") (pinfunction "A_A") (pintype "passive"))
      (node (ref "IR_S_RIGHT") (pin "A") (pinfunction "A_A") (pintype "passive"))
      (node (ref "JP1") (pin "1") (pinfunction "1_1") (pintype "passive"))
      (node (ref "LASER") (pin "3") (pinfunction "3_3") (pintype "passive"))
      (node (ref "LASER1") (pin "3") (pinfunction "3_3") (pintype "passive"))
      (node (ref "LED11") (pin "C") (pinfunction "C_C") (pintype "passive"))
      (node (ref "LED12") (pin "C") (pinfunction "C_C") (pintype "passive"))
      (node (ref "LED9") (pin "A") (pinfunction "A_A") (pintype "passive"))
      (node (ref "LSM6DS0") (pin "P$10") (pinfunction "RES2_P$10") (pintype "bidirectional"))
      (node (ref "LSM6DS0") (pin "P$11") (pinfunction "RES3_P$11") (pintype "bidirectional"))
      (node (ref "LSM6DS0") (pin "P$12") (pinfunction "GND_P$12") (pintype "power_in"))
      (node (ref "LSM6DS0") (pin "P$13") (pinfunction "GND_P$13") (pintype "power_in"))
      (node (ref "LSM6DS0") (pin "P$15") (pinfunction "RES4_P$15") (pintype "bidirectional"))
      (node (ref "LSM6DS0") (pin "P$4") (pinfunction "SDO_P$4") (pintype "bidirectional"))
      (node (ref "LSM6DS0") (pin "P$8") (pinfunction "DEN_P$8") (pintype "bidirectional"))
      (node (ref "LSM6DS0") (pin "P$9") (pinfunction "RES1_P$9") (pintype "bidirectional"))
      (node (ref "Q2") (pin "2") (pinfunction "S_2") (pintype "passive"))
      (node (ref "Q3") (pin "2") (pinfunction "S_2") (pintype "passive"))
      (node (ref "R3") (pin "1") (pinfunction "1_1") (pintype "passive"))
      (node (ref "R30") (pin "1") (pinfunction "1_1") (pintype "passive"))
      (node (ref "R4") (pin "2") (pinfunction "2_2") (pintype "passive"))
      (node (ref "RESET") (pin "1") (pinfunction "1_1") (pintype "passive"))
      (node (ref "RESET") (pin "2") (pinfunction "2_2") (pintype "passive"))
      (node (ref "TP2") (pin "TP") (pinfunction "TP_TP") (pintype "input"))
      (node (ref "U$10") (pin "P$2") (pinfunction "C_P$2") (pintype "bidirectional"))
      (node (ref "U$11") (pin "P$6") (pinfunction "GND_P$6") (pintype "bidirectional"))
      (node (ref "U$12") (pin "P$6") (pinfunction "GND_P$6") (pintype "bidirectional"))
      (node (ref "U$3") (pin "P$2") (pinfunction "C_P$2") (pintype "bidirectional"))
      (node (ref "U$4") (pin "P$2") (pinfunction "C_P$2") (pintype "bidirectional"))
      (node (ref "U$5") (pin "P$2") (pinfunction "C_P$2") (pintype "bidirectional"))
      (node (ref "U$6") (pin "P$2") (pinfunction "C_P$2") (pintype "bidirectional"))
      (node (ref "U$7") (pin "P$2") (pinfunction "C_P$2") (pintype "bidirectional"))
      (node (ref "U$8") (pin "P$2") (pinfunction "C_P$2") (pintype "bidirectional"))
      (node (ref "U$9") (pin "P$2") (pinfunction "C_P$2") (pintype "bidirectional"))
      (node (ref "U1") (pin "12") (pinfunction "GND_12") (pintype "bidirectional"))
      (node (ref "U1") (pin "2") (pinfunction "GND_2") (pintype "bidirectional"))
      (node (ref "U1") (pin "3") (pinfunction "GND_3") (pintype "bidirectional"))
      (node (ref "U1") (pin "4") (pinfunction "GND_4") (pintype "bidirectional"))
      (node (ref "U1") (pin "6") (pinfunction "GND_6") (pintype "bidirectional"))
      (node (ref "U2") (pin "10") (pinfunction "VSS_2_10") (pintype "passive"))
      (node (ref "U2") (pin "19") (pinfunction "VSSA_19") (pintype "passive"))
      (node (ref "U2") (pin "26") (pinfunction "VSS_26") (pintype "passive"))
      (node (ref "U2") (pin "49") (pinfunction "VSS_4_49") (pintype "power_in"))
      (node (ref "U2") (pin "74") (pinfunction "VSS_2_74") (pintype "passive"))
      (node (ref "U2") (pin "99") (pinfunction "VSS_99") (pintype "passive"))
      (node (ref "UART") (pin "4") (pinfunction "4_4") (pintype "passive"))
      (node (ref "USER") (pin "1") (pinfunction "1_1") (pintype "passive"))
      (node (ref "USER") (pin "2") (pinfunction "2_2") (pintype "passive"))
      (node (ref "X1") (pin "5") (pinfunction "5_5") (pintype "passive"))
      (node (ref "X2") (pin "1") (pinfunction "1_1") (pintype "passive"))
      (node (ref "X2") (pin "10") (pinfunction "1_10") (pintype "passive"))
    )
    (net (code "45") (name "Net-(C16-Pad1)") (class "Default")
      (node (ref "C16") (pin "1") (pinfunction "1_1") (pintype "passive"))
      (node (ref "R8") (pin "1") (pinfunction "1_1") (pintype "passive"))
      (node (ref "X1") (pin "3") (pinfunction "3_3") (pintype "passive"))
    )
    (net (code "46") (name "Net-(C17-Pad2)") (class "Default")
      (node (ref "C17") (pin "2") (pinfunction "2_2") (pintype "passive"))
      (node (ref "C18") (pin "2") (pinfunction "2_2") (pintype "passive"))
      (node (ref "LASER1") (pin "4") (pinfunction "4_4") (pintype "passive"))
      (node (ref "R35") (pin "2") (pinfunction "2_2") (pintype "passive"))
      (node (ref "U1") (pin "1") (pinfunction "VCC_1") (pintype "bidirectional"))
      (node (ref "U1") (pin "11") (pinfunction "VCC_11") (pintype "bidirectional"))
    )
    (net (code "47") (name "Net-(C20-Pad2)") (class "Default")
      (node (ref "C20") (pin "2") (pinfunction "2_2") (pintype "passive"))
      (node (ref "R7") (pin "1") (pinfunction "1_1") (pintype "passive"))
      (node (ref "X1") (pin "2") (pinfunction "2_2") (pintype "passive"))
    )
    (net (code "48") (name "Net-(D1-PadA)") (class "Default")
      (node (ref "D1") (pin "A") (pinfunction "A_A") (pintype "passive"))
      (node (ref "X1") (pin "1") (pinfunction "1_1") (pintype "passive"))
    )
    (net (code "49") (name "Net-(IO1-AOUT1)") (class "Default")
      (node (ref "IO1") (pin "4") (pinfunction "AOUT1_4") (pintype "bidirectional"))
      (node (ref "U$12") (pin "P$1") (pinfunction "P$1_P$1") (pintype "bidirectional"))
    )
    (net (code "50") (name "Net-(IO1-AOUT2)") (class "Default")
      (node (ref "IO1") (pin "6") (pinfunction "AOUT2_6") (pintype "bidirectional"))
      (node (ref "U$12") (pin "P$2") (pinfunction "P$2_P$2") (pintype "bidirectional"))
    )
    (net (code "51") (name "Net-(IO1-AVREF)") (class "Default")
      (node (ref "IO1") (pin "22") (pinfunction "AVREF_22") (pintype "bidirectional"))
      (node (ref "IO1") (pin "23") (pinfunction "BVREF_23") (pintype "bidirectional"))
      (node (ref "IO1") (pin "24") (pinfunction "VREFO_24") (pintype "bidirectional"))
    )
    (net (code "52") (name "Net-(IO1-BOUT1)") (class "Default")
      (node (ref "IO1") (pin "9") (pinfunction "BOUT1_9") (pintype "bidirectional"))
      (node (ref "U$11") (pin "P$2") (pinfunction "P$2_P$2") (pintype "bidirectional"))
    )
    (net (code "53") (name "Net-(IO1-BOUT2)") (class "Default")
      (node (ref "IO1") (pin "7") (pinfunction "BOUT2_7") (pintype "bidirectional"))
      (node (ref "U$11") (pin "P$1") (pinfunction "P$1_P$1") (pintype "bidirectional"))
    )
    (net (code "54") (name "Net-(IO1-NSLEEP)") (class "Default")
      (node (ref "IO1") (pin "1") (pinfunction "NSLEEP_1") (pintype "bidirectional"))
      (node (ref "R1") (pin "2") (pinfunction "2_2") (pintype "passive"))
    )
    (net (code "55") (name "Net-(IO1-VCP)") (class "Default")
      (node (ref "C3") (pin "2") (pinfunction "2_2") (pintype "passive"))
      (node (ref "IO1") (pin "17") (pinfunction "VCP_17") (pintype "bidirectional"))
    )
    (net (code "56") (name "Net-(IO1-VINT)") (class "Default")
      (node (ref "C4") (pin "2") (pinfunction "2_2") (pintype "passive"))
      (node (ref "IO1") (pin "20") (pinfunction "VINT_20") (pintype "bidirectional"))
    )
    (net (code "57") (name "Net-(IR_LEFT-PadA)") (class "Default")
      (node (ref "IR_LEFT") (pin "A") (pinfunction "A_A") (pintype "passive"))
      (node (ref "R33") (pin "1") (pinfunction "1_1") (pintype "passive"))
    )
    (net (code "58") (name "Net-(IR_RIGHT-PadA)") (class "Default")
      (node (ref "IR_RIGHT") (pin "A") (pinfunction "A_A") (pintype "passive"))
      (node (ref "R31") (pin "1") (pinfunction "1_1") (pintype "passive"))
    )
    (net (code "59") (name "Net-(LED1-PadA)") (class "Default")
      (node (ref "LED1") (pin "A") (pinfunction "A_A") (pintype "passive"))
      (node (ref "R5") (pin "1") (pinfunction "1_1") (pintype "passive"))
    )
    (net (code "60") (name "Net-(LED2-PadA)") (class "Default")
      (node (ref "LED2") (pin "A") (pinfunction "A_A") (pintype "passive"))
      (node (ref "R10") (pin "1") (pinfunction "1_1") (pintype "passive"))
    )
    (net (code "61") (name "Net-(LED3-PadA)") (class "Default")
      (node (ref "LED3") (pin "A") (pinfunction "A_A") (pintype "passive"))
      (node (ref "R12") (pin "1") (pinfunction "1_1") (pintype "passive"))
    )
    (net (code "62") (name "Net-(LED4-PadA)") (class "Default")
      (node (ref "LED4") (pin "A") (pinfunction "A_A") (pintype "passive"))
      (node (ref "R17") (pin "1") (pinfunction "1_1") (pintype "passive"))
    )
    (net (code "63") (name "Net-(LED5-PadA)") (class "Default")
      (node (ref "LED5") (pin "A") (pinfunction "A_A") (pintype "passive"))
      (node (ref "R19") (pin "1") (pinfunction "1_1") (pintype "passive"))
    )
    (net (code "64") (name "Net-(LED6-PadA)") (class "Default")
      (node (ref "LED6") (pin "A") (pinfunction "A_A") (pintype "passive"))
      (node (ref "R21") (pin "1") (pinfunction "1_1") (pintype "passive"))
    )
    (net (code "65") (name "Net-(LED7-PadA)") (class "Default")
      (node (ref "LED7") (pin "A") (pinfunction "A_A") (pintype "passive"))
      (node (ref "R23") (pin "1") (pinfunction "1_1") (pintype "passive"))
    )
    (net (code "66") (name "Net-(LED8-PadA)") (class "Default")
      (node (ref "LED8") (pin "A") (pinfunction "A_A") (pintype "passive"))
      (node (ref "R25") (pin "1") (pinfunction "1_1") (pintype "passive"))
    )
    (net (code "67") (name "Net-(LED10-PadA)") (class "Default")
      (node (ref "LED10") (pin "A") (pinfunction "A_A") (pintype "passive"))
      (node (ref "R29") (pin "1") (pinfunction "1_1") (pintype "passive"))
    )
    (net (code "68") (name "Net-(LED11-PadA)") (class "Default")
      (node (ref "LED11") (pin "A") (pinfunction "A_A") (pintype "passive"))
      (node (ref "R28") (pin "1") (pinfunction "1_1") (pintype "passive"))
    )
    (net (code "69") (name "Net-(LED12-PadA)") (class "Default")
      (node (ref "LED12") (pin "A") (pinfunction "A_A") (pintype "passive"))
      (node (ref "R27") (pin "2") (pinfunction "2_2") (pintype "passive"))
    )
    (net (code "70") (name "Net-(LSM6DS0-CAP)") (class "Default")
      (node (ref "C14") (pin "2") (pinfunction "2_2") (pintype "passive"))
      (node (ref "LSM6DS0") (pin "P$14") (pinfunction "CAP_P$14") (pintype "bidirectional"))
    )
    (net (code "71") (name "Net-(U1-SCL)") (class "Default")
      (node (ref "LASER1") (pin "2") (pinfunction "2_2") (pintype "passive"))
      (node (ref "U1") (pin "10") (pinfunction "SCL_10") (pintype "bidirectional"))
    )
    (net (code "72") (name "Net-(U1-SDA)") (class "Default")
      (node (ref "LASER1") (pin "1") (pinfunction "1_1") (pintype "passive"))
      (node (ref "U1") (pin "9") (pinfunction "SDA_9") (pintype "bidirectional"))
    )
    (net (code "73") (name "Net-(U1-~{SHUT})") (class "Default")
      (node (ref "R35") (pin "1") (pinfunction "1_1") (pintype "passive"))
      (node (ref "U1") (pin "5") (pinfunction "~{SHUT}_5") (pintype "bidirectional"))
    )
    (net (code "74") (name "Net-(U2A-VCAP_1)") (class "Default")
      (node (ref "C23") (pin "2") (pinfunction "2_2") (pintype "passive"))
      (node (ref "U2") (pin "48") (pinfunction "VCAP_1_48") (pintype "power_in"))
    )
    (net (code "75") (name "Net-(U2B-VCAP_2)") (class "Default")
      (node (ref "C19") (pin "1") (pinfunction "1_1") (pintype "passive"))
      (node (ref "U2") (pin "73") (pinfunction "VCAP_2_73") (pintype "power_in"))
    )
    (net (code "76") (name "VCC") (class "Default")
      (node (ref "C1") (pin "1") (pinfunction "1_1") (pintype "passive"))
      (node (ref "C10") (pin "1") (pinfunction "1_1") (pintype "passive"))
      (node (ref "C2") (pin "1") (pinfunction "1_1") (pintype "passive"))
      (node (ref "C3") (pin "1") (pinfunction "1_1") (pintype "passive"))
      (node (ref "C7") (pin "+") (pinfunction "+_+") (pintype "passive"))
      (node (ref "C9") (pin "1") (pinfunction "1_1") (pintype "passive"))
      (node (ref "D1") (pin "C") (pinfunction "C_C") (pintype "passive"))
      (node (ref "IC2") (pin "1") (pinfunction "VI_1") (pintype "input"))
      (node (ref "IO1") (pin "18") (pinfunction "VM_18") (pintype "bidirectional"))
      (node (ref "IO1") (pin "19") (pinfunction "VM1_19") (pintype "bidirectional"))
      (node (ref "JP1") (pin "2") (pinfunction "2_2") (pintype "passive"))
      (node (ref "R1") (pin "1") (pinfunction "1_1") (pintype "passive"))
      (node (ref "R29") (pin "2") (pinfunction "2_2") (pintype "passive"))
      (node (ref "R31") (pin "2") (pinfunction "2_2") (pintype "passive"))
      (node (ref "R33") (pin "2") (pinfunction "2_2") (pintype "passive"))
    )
    (net (code "77") (name "unconnected-(IO1-NFAULT-Pad16)") (class "Default")
      (node (ref "IO1") (pin "16") (pinfunction "NFAULT_16") (pintype "bidirectional"))
    )
    (net (code "78") (name "unconnected-(LSM6DS0-DRDY{slash}INT2-PadP$6)") (class "Default")
      (node (ref "LSM6DS0") (pin "P$6") (pinfunction "DRDY/INT2_P$6") (pintype "bidirectional"))
    )
    (net (code "79") (name "unconnected-(LSM6DS0-INT1-PadP$7)") (class "Default")
      (node (ref "LSM6DS0") (pin "P$7") (pinfunction "INT1_P$7") (pintype "bidirectional"))
    )
    (net (code "80") (name "unconnected-(U1-~{INT}-Pad7)") (class "Default")
      (node (ref "U1") (pin "7") (pinfunction "~{INT}_7") (pintype "bidirectional"))
    )
    (net (code "81") (name "unconnected-(U2A-PB10-Pad46)") (class "Default")
      (node (ref "U2") (pin "46") (pinfunction "PB10_46") (pintype "bidirectional"))
    )
    (net (code "82") (name "unconnected-(U2A-PB11-Pad47)") (class "Default")
      (node (ref "U2") (pin "47") (pinfunction "PB11_47") (pintype "bidirectional"))
    )
    (net (code "83") (name "unconnected-(U2A-PC0-Pad15)") (class "Default")
      (node (ref "U2") (pin "15") (pinfunction "PC0_15") (pintype "bidirectional"))
    )
    (net (code "84") (name "unconnected-(U2A-PC1-Pad16)") (class "Default")
      (node (ref "U2") (pin "16") (pinfunction "PC1_16") (pintype "bidirectional"))
    )
    (net (code "85") (name "unconnected-(U2A-PC2-Pad17)") (class "Default")
      (node (ref "U2") (pin "17") (pinfunction "PC2_17") (pintype "bidirectional"))
    )
    (net (code "86") (name "unconnected-(U2A-PC3-Pad18)") (class "Default")
      (node (ref "U2") (pin "18") (pinfunction "PC3_18") (pintype "bidirectional"))
    )
    (net (code "87") (name "unconnected-(U2A-PC13-Pad7)") (class "Default")
      (node (ref "U2") (pin "7") (pinfunction "PC13_7") (pintype "bidirectional"))
    )
    (net (code "88") (name "unconnected-(U2A-PC14-Pad8)") (class "Default")
      (node (ref "U2") (pin "8") (pinfunction "PC14_8") (pintype "bidirectional"))
    )
    (net (code "89") (name "unconnected-(U2A-PC15-Pad9)") (class "Default")
      (node (ref "U2") (pin "9") (pinfunction "PC15_9") (pintype "bidirectional"))
    )
    (net (code "90") (name "unconnected-(U2A-PE2-Pad1)") (class "Default")
      (node (ref "U2") (pin "1") (pinfunction "PE2_1") (pintype "bidirectional"))
    )
    (net (code "91") (name "unconnected-(U2A-PE4-Pad3)") (class "Default")
      (node (ref "U2") (pin "3") (pinfunction "PE4_3") (pintype "bidirectional"))
    )
    (net (code "92") (name "unconnected-(U2A-PE5-Pad4)") (class "Default")
      (node (ref "U2") (pin "4") (pinfunction "PE5_4") (pintype "bidirectional"))
    )
    (net (code "93") (name "unconnected-(U2A-PE6-Pad5)") (class "Default")
      (node (ref "U2") (pin "5") (pinfunction "PE6_5") (pintype "bidirectional"))
    )
    (net (code "94") (name "unconnected-(U2A-PE15-Pad45)") (class "Default")
      (node (ref "U2") (pin "45") (pinfunction "PE15_45") (pintype "bidirectional"))
    )
    (net (code "95") (name "unconnected-(U2B-PA8-Pad67)") (class "Default")
      (node (ref "U2") (pin "67") (pinfunction "PA8_67") (pintype "bidirectional"))
    )
    (net (code "96") (name "unconnected-(U2B-PA13-Pad72)") (class "Default")
      (node (ref "U2") (pin "72") (pinfunction "PA13_72") (pintype "bidirectional"))
    )
    (net (code "97") (name "unconnected-(U2B-PA14-Pad76)") (class "Default")
      (node (ref "U2") (pin "76") (pinfunction "PA14_76") (pintype "bidirectional"))
    )
    (net (code "98") (name "unconnected-(U2B-PA15-Pad77)") (class "Default")
      (node (ref "U2") (pin "77") (pinfunction "PA15_77") (pintype "bidirectional"))
    )
    (net (code "99") (name "unconnected-(U2B-PB3-Pad89)") (class "Default")
      (node (ref "U2") (pin "89") (pinfunction "PB3_89") (pintype "bidirectional"))
    )
    (net (code "100") (name "unconnected-(U2B-PB7-Pad93)") (class "Default")
      (node (ref "U2") (pin "93") (pinfunction "PB7_93") (pintype "bidirectional"))
    )
    (net (code "101") (name "unconnected-(U2B-PB8-Pad95)") (class "Default")
      (node (ref "U2") (pin "95") (pinfunction "PB8_95") (pintype "bidirectional"))
    )
    (net (code "102") (name "unconnected-(U2B-PB9-Pad96)") (class "Default")
      (node (ref "U2") (pin "96") (pinfunction "PB9_96") (pintype "bidirectional"))
    )
    (net (code "103") (name "unconnected-(U2B-PB12-Pad51)") (class "Default")
      (node (ref "U2") (pin "51") (pinfunction "PB12_51") (pintype "bidirectional"))
    )
    (net (code "104") (name "unconnected-(U2B-PB13-Pad52)") (class "Default")
      (node (ref "U2") (pin "52") (pinfunction "PB13_52") (pintype "bidirectional"))
    )
    (net (code "105") (name "unconnected-(U2B-PB14-Pad53)") (class "Default")
      (node (ref "U2") (pin "53") (pinfunction "PB14_53") (pintype "bidirectional"))
    )
    (net (code "106") (name "unconnected-(U2B-PB15-Pad54)") (class "Default")
      (node (ref "U2") (pin "54") (pinfunction "PB15_54") (pintype "bidirectional"))
    )
    (net (code "107") (name "unconnected-(U2B-PC8-Pad65)") (class "Default")
      (node (ref "U2") (pin "65") (pinfunction "PC8_65") (pintype "bidirectional"))
    )
    (net (code "108") (name "unconnected-(U2B-PC9-Pad66)") (class "Default")
      (node (ref "U2") (pin "66") (pinfunction "PC9_66") (pintype "bidirectional"))
    )
    (net (code "109") (name "unconnected-(U2B-PC10-Pad78)") (class "Default")
      (node (ref "U2") (pin "78") (pinfunction "PC10_78") (pintype "bidirectional"))
    )
    (net (code "110") (name "unconnected-(U2B-PC11-Pad79)") (class "Default")
      (node (ref "U2") (pin "79") (pinfunction "PC11_79") (pintype "bidirectional"))
    )
    (net (code "111") (name "unconnected-(U2B-PD3-Pad84)") (class "Default")
      (node (ref "U2") (pin "84") (pinfunction "PD3_84") (pintype "bidirectional"))
    )
    (net (code "112") (name "unconnected-(U2B-PD4-Pad85)") (class "Default")
      (node (ref "U2") (pin "85") (pinfunction "PD4_85") (pintype "bidirectional"))
    )
    (net (code "113") (name "unconnected-(U2B-PD5-Pad86)") (class "Default")
      (node (ref "U2") (pin "86") (pinfunction "PD5_86") (pintype "bidirectional"))
    )
    (net (code "114") (name "unconnected-(U2B-PD6-Pad87)") (class "Default")
      (node (ref "U2") (pin "87") (pinfunction "PD6_87") (pintype "bidirectional"))
    )
    (net (code "115") (name "unconnected-(U2B-PD7-Pad88)") (class "Default")
      (node (ref "U2") (pin "88") (pinfunction "PD7_88") (pintype "bidirectional"))
    )
    (net (code "116") (name "unconnected-(U2B-PD8-Pad55)") (class "Default")
      (node (ref "U2") (pin "55") (pinfunction "PD8_55") (pintype "bidirectional"))
    )
    (net (code "117") (name "unconnected-(U2B-PD9-Pad56)") (class "Default")
      (node (ref "U2") (pin "56") (pinfunction "PD9_56") (pintype "bidirectional"))
    )
    (net (code "118") (name "unconnected-(U2B-PD10-Pad57)") (class "Default")
      (node (ref "U2") (pin "57") (pinfunction "PD10_57") (pintype "bidirectional"))
    )
    (net (code "119") (name "unconnected-(U2B-PD11-Pad58)") (class "Default")
      (node (ref "U2") (pin "58") (pinfunction "PD11_58") (pintype "bidirectional"))
    )
    (net (code "120") (name "unconnected-(U2B-PD12-Pad59)") (class "Default")
      (node (ref "U2") (pin "59") (pinfunction "PD12_59") (pintype "bidirectional"))
    )
    (net (code "121") (name "unconnected-(U2B-PD13-Pad60)") (class "Default")
      (node (ref "U2") (pin "60") (pinfunction "PD13_60") (pintype "bidirectional"))
    )
    (net (code "122") (name "unconnected-(U2B-PD14-Pad61)") (class "Default")
      (node (ref "U2") (pin "61") (pinfunction "PD14_61") (pintype "bidirectional"))
    )
    (net (code "123") (name "unconnected-(U2B-PD15-Pad62)") (class "Default")
      (node (ref "U2") (pin "62") (pinfunction "PD15_62") (pintype "bidirectional"))
    )
    (net (code "124") (name "unconnected-(U2B-PE0-Pad97)") (class "Default")
      (node (ref "U2") (pin "97") (pinfunction "PE0_97") (pintype "bidirectional"))
    )
    (net (code "125") (name "unconnected-(U2B-PE1-Pad98)") (class "Default")
      (node (ref "U2") (pin "98") (pinfunction "PE1_98") (pintype "bidirectional"))
    )
    (net (code "126") (name "unconnected-(USER-Pad4)") (class "Default")
      (node (ref "USER") (pin "4") (pinfunction "4_4") (pintype "passive"))
    )
    (net (code "127") (name "unconnected-(X1-Pad4)") (class "Default")
      (node (ref "X1") (pin "4") (pinfunction "4_4") (pintype "passive"))
    )
  )
)
